# Bank0.net
KiCad netlist of a schematic drawn in Altium Designer
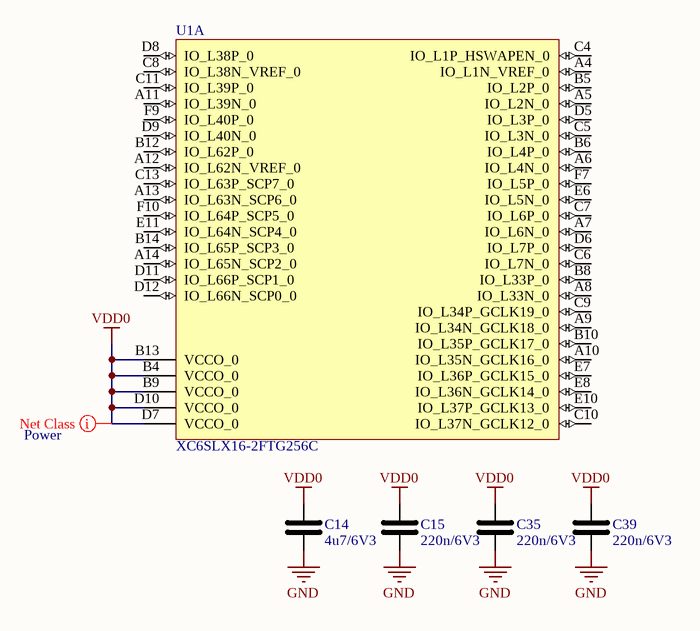
[diagram p0: Bank0.SchDoc]

(export (version "E")
  (design (tool "Eeschema 10.0.6"))
  (components
    (comp (ref "C14") (value "4u7/6V3") (footprint "C0805_N") (libsource (lib "niceCircuits") (part "C")))
    (comp (ref "C15") (value "220n/6V3") (footprint "C0402_N") (libsource (lib "niceCircuits") (part "C")))
    (comp (ref "C35") (value "220n/6V3") (footprint "C0402_N") (libsource (lib "niceCircuits") (part "C")))
    (comp (ref "C39") (value "220n/6V3") (footprint "C0402_N") (libsource (lib "niceCircuits") (part "C")))
    (comp (ref "U1")
      (value "XC6SLX16-2FTG256C")
      (footprint "Xilinx_FT256_L")
      (libsource (lib "niceCircuits") (part "XC6SLX16-2FTG256C"))
    )
  )
  (nets
    (net (code "1") (name "GND") (class "Default")
      (node (ref "C14") (pin "1") (pinfunction "1_1") (pintype "passive"))
      (node (ref "C15") (pin "1") (pinfunction "1_1") (pintype "passive"))
      (node (ref "C35") (pin "1") (pinfunction "1_1") (pintype "passive"))
      (node (ref "C39") (pin "1") (pinfunction "1_1") (pintype "passive"))
    )
    (net (code "2") (name "VDD0") (class "Default")
      (node (ref "C14") (pin "2") (pinfunction "2_2") (pintype "passive"))
      (node (ref "C15") (pin "2") (pinfunction "2_2") (pintype "passive"))
      (node (ref "C35") (pin "2") (pinfunction "2_2") (pintype "passive"))
      (node (ref "C39") (pin "2") (pinfunction "2_2") (pintype "passive"))
      (node (ref "U1") (pin "B13") (pinfunction "VCCO_0_B13") (pintype "power_in"))
      (node (ref "U1") (pin "B4") (pinfunction "VCCO_0_B4") (pintype "power_in"))
      (node (ref "U1") (pin "B9") (pinfunction "VCCO_0_B9") (pintype "power_in"))
      (node (ref "U1") (pin "D10") (pinfunction "VCCO_0_D10") (pintype "power_in"))
      (node (ref "U1") (pin "D7") (pinfunction "VCCO_0_D7") (pintype "power_in"))
    )
    (net (code "3") (name "unconnected-(U1A-IO_L1N_VREF_0-PadA4)") (class "Default")
      (node (ref "U1") (pin "A4") (pinfunction "IO_L1N_VREF_0_A4") (pintype "bidirectional"))
    )
    (net (code "4") (name "unconnected-(U1A-IO_L1P_HSWAPEN_0-PadC4)") (class "Default")
      (node (ref "U1") (pin "C4") (pinfunction "IO_L1P_HSWAPEN_0_C4") (pintype "bidirectional"))
    )
    (net (code "5") (name "unconnected-(U1A-IO_L2N_0-PadA5)") (class "Default")
      (node (ref "U1") (pin "A5") (pinfunction "IO_L2N_0_A5") (pintype "bidirectional"))
    )
    (net (code "6") (name "unconnected-(U1A-IO_L2P_0-PadB5)") (class "Default")
      (node (ref "U1") (pin "B5") (pinfunction "IO_L2P_0_B5") (pintype "bidirectional"))
    )
    (net (code "7") (name "unconnected-(U1A-IO_L3N_0-PadC5)") (class "Default")
      (node (ref "U1") (pin "C5") (pinfunction "IO_L3N_0_C5") (pintype "bidirectional"))
    )
    (net (code "8") (name "unconnected-(U1A-IO_L3P_0-PadD5)") (class "Default")
      (node (ref "U1") (pin "D5") (pinfunction "IO_L3P_0_D5") (pintype "bidirectional"))
    )
    (net (code "9") (name "unconnected-(U1A-IO_L4N_0-PadA6)") (class "Default")
      (node (ref "U1") (pin "A6") (pinfunction "IO_L4N_0_A6") (pintype "bidirectional"))
    )
    (net (code "10") (name "unconnected-(U1A-IO_L4P_0-PadB6)") (class "Default")
      (node (ref "U1") (pin "B6") (pinfunction "IO_L4P_0_B6") (pintype "bidirectional"))
    )
    (net (code "11") (name "unconnected-(U1A-IO_L5N_0-PadE6)") (class "Default")
      (node (ref "U1") (pin "E6") (pinfunction "IO_L5N_0_E6") (pintype "bidirectional"))
    )
    (net (code "12") (name "unconnected-(U1A-IO_L5P_0-PadF7)") (class "Default")
      (node (ref "U1") (pin "F7") (pinfunction "IO_L5P_0_F7") (pintype "bidirectional"))
    )
    (net (code "13") (name "unconnected-(U1A-IO_L6N_0-PadA7)") (class "Default")
      (node (ref "U1") (pin "A7") (pinfunction "IO_L6N_0_A7") (pintype "bidirectional"))
    )
    (net (code "14") (name "unconnected-(U1A-IO_L6P_0-PadC7)") (class "Default")
      (node (ref "U1") (pin "C7") (pinfunction "IO_L6P_0_C7") (pintype "bidirectional"))
    )
    (net (code "15") (name "unconnected-(U1A-IO_L7N_0-PadC6)") (class "Default")
      (node (ref "U1") (pin "C6") (pinfunction "IO_L7N_0_C6") (pintype "bidirectional"))
    )
    (net (code "16") (name "unconnected-(U1A-IO_L7P_0-PadD6)") (class "Default")
      (node (ref "U1") (pin "D6") (pinfunction "IO_L7P_0_D6") (pintype "bidirectional"))
    )
    (net (code "17") (name "unconnected-(U1A-IO_L33N_0-PadA8)") (class "Default")
      (node (ref "U1") (pin "A8") (pinfunction "IO_L33N_0_A8") (pintype "bidirectional"))
    )
    (net (code "18") (name "unconnected-(U1A-IO_L33P_0-PadB8)") (class "Default")
      (node (ref "U1") (pin "B8") (pinfunction "IO_L33P_0_B8") (pintype "bidirectional"))
    )
    (net (code "19") (name "unconnected-(U1A-IO_L34N_GCLK18_0-PadA9)") (class "Default")
      (node (ref "U1") (pin "A9") (pinfunction "IO_L34N_GCLK18_0_A9") (pintype "bidirectional"))
    )
    (net (code "20") (name "unconnected-(U1A-IO_L34P_GCLK19_0-PadC9)") (class "Default")
      (node (ref "U1") (pin "C9") (pinfunction "IO_L34P_GCLK19_0_C9") (pintype "bidirectional"))
    )
    (net (code "21") (name "unconnected-(U1A-IO_L35N_GCLK16_0-PadA10)") (class "Default")
      (node (ref "U1") (pin "A10") (pinfunction "IO_L35N_GCLK16_0_A10") (pintype "bidirectional"))
    )
    (net (code "22") (name "unconnected-(U1A-IO_L35P_GCLK17_0-PadB10)") (class "Default")
      (node (ref "U1") (pin "B10") (pinfunction "IO_L35P_GCLK17_0_B10") (pintype "bidirectional"))
    )
    (net (code "23") (name "unconnected-(U1A-IO_L36N_GCLK14_0-PadE8)") (class "Default")
      (node (ref "U1") (pin "E8") (pinfunction "IO_L36N_GCLK14_0_E8") (pintype "bidirectional"))
    )
    (net (code "24") (name "unconnected-(U1A-IO_L36P_GCLK15_0-PadE7)") (class "Default")
      (node (ref "U1") (pin "E7") (pinfunction "IO_L36P_GCLK15_0_E7") (pintype "bidirectional"))
    )
    (net (code "25") (name "unconnected-(U1A-IO_L37N_GCLK12_0-PadC10)") (class "Default")
      (node (ref "U1") (pin "C10") (pinfunction "IO_L37N_GCLK12_0_C10") (pintype "bidirectional"))
    )
    (net (code "26") (name "unconnected-(U1A-IO_L37P_GCLK13_0-PadE10)") (class "Default")
      (node (ref "U1") (pin "E10") (pinfunction "IO_L37P_GCLK13_0_E10") (pintype "bidirectional"))
    )
    (net (code "27") (name "unconnected-(U1A-IO_L38N_VREF_0-PadC8)") (class "Default")
      (node (ref "U1") (pin "C8") (pinfunction "IO_L38N_VREF_0_C8") (pintype "bidirectional"))
    )
    (net (code "28") (name "unconnected-(U1A-IO_L38P_0-PadD8)") (class "Default")
      (node (ref "U1") (pin "D8") (pinfunction "IO_L38P_0_D8") (pintype "bidirectional"))
    )
    (net (code "29") (name "unconnected-(U1A-IO_L39N_0-PadA11)") (class "Default")
      (node (ref "U1") (pin "A11") (pinfunction "IO_L39N_0_A11") (pintype "bidirectional"))
    )
    (net (code "30") (name "unconnected-(U1A-IO_L39P_0-PadC11)") (class "Default")
      (node (ref "U1") (pin "C11") (pinfunction "IO_L39P_0_C11") (pintype "bidirectional"))
    )
    (net (code "31") (name "unconnected-(U1A-IO_L40N_0-PadD9)") (class "Default")
      (node (ref "U1") (pin "D9") (pinfunction "IO_L40N_0_D9") (pintype "bidirectional"))
    )
    (net (code "32") (name "unconnected-(U1A-IO_L40P_0-PadF9)") (class "Default")
      (node (ref "U1") (pin "F9") (pinfunction "IO_L40P_0_F9") (pintype "bidirectional"))
    )
    (net (code "33") (name "unconnected-(U1A-IO_L62N_VREF_0-PadA12)") (class "Default")
      (node (ref "U1") (pin "A12") (pinfunction "IO_L62N_VREF_0_A12") (pintype "bidirectional"))
    )
    (net (code "34") (name "unconnected-(U1A-IO_L62P_0-PadB12)") (class "Default")
      (node (ref "U1") (pin "B12") (pinfunction "IO_L62P_0_B12") (pintype "bidirectional"))
    )
    (net (code "35") (name "unconnected-(U1A-IO_L63N_SCP6_0-PadA13)") (class "Default")
      (node (ref "U1") (pin "A13") (pinfunction "IO_L63N_SCP6_0_A13") (pintype "bidirectional"))
    )
    (net (code "36") (name "unconnected-(U1A-IO_L63P_SCP7_0-PadC13)") (class "Default")
      (node (ref "U1") (pin "C13") (pinfunction "IO_L63P_SCP7_0_C13") (pintype "bidirectional"))
    )
    (net (code "37") (name "unconnected-(U1A-IO_L64N_SCP4_0-PadE11)") (class "Default")
      (node (ref "U1") (pin "E11") (pinfunction "IO_L64N_SCP4_0_E11") (pintype "bidirectional"))
    )
    (net (code "38") (name "unconnected-(U1A-IO_L64P_SCP5_0-PadF10)") (class "Default")
      (node (ref "U1") (pin "F10") (pinfunction "IO_L64P_SCP5_0_F10") (pintype "bidirectional"))
    )
    (net (code "39") (name "unconnected-(U1A-IO_L65N_SCP2_0-PadA14)") (class "Default")
      (node (ref "U1") (pin "A14") (pinfunction "IO_L65N_SCP2_0_A14") (pintype "bidirectional"))
    )
    (net (code "40") (name "unconnected-(U1A-IO_L65P_SCP3_0-PadB14)") (class "Default")
      (node (ref "U1") (pin "B14") (pinfunction "IO_L65P_SCP3_0_B14") (pintype "bidirectional"))
    )
    (net (code "41") (name "unconnected-(U1A-IO_L66N_SCP0_0-PadD12)") (class "Default")
      (node (ref "U1") (pin "D12") (pinfunction "IO_L66N_SCP0_0_D12") (pintype "bidirectional"))
    )
    (net (code "42") (name "unconnected-(U1A-IO_L66P_SCP1_0-PadD11)") (class "Default")
      (node (ref "U1") (pin "D11") (pinfunction "IO_L66P_SCP1_0_D11") (pintype "bidirectional"))
    )
  )
)
